# Power.net
KiCad netlist of a schematic drawn in Altium Designer
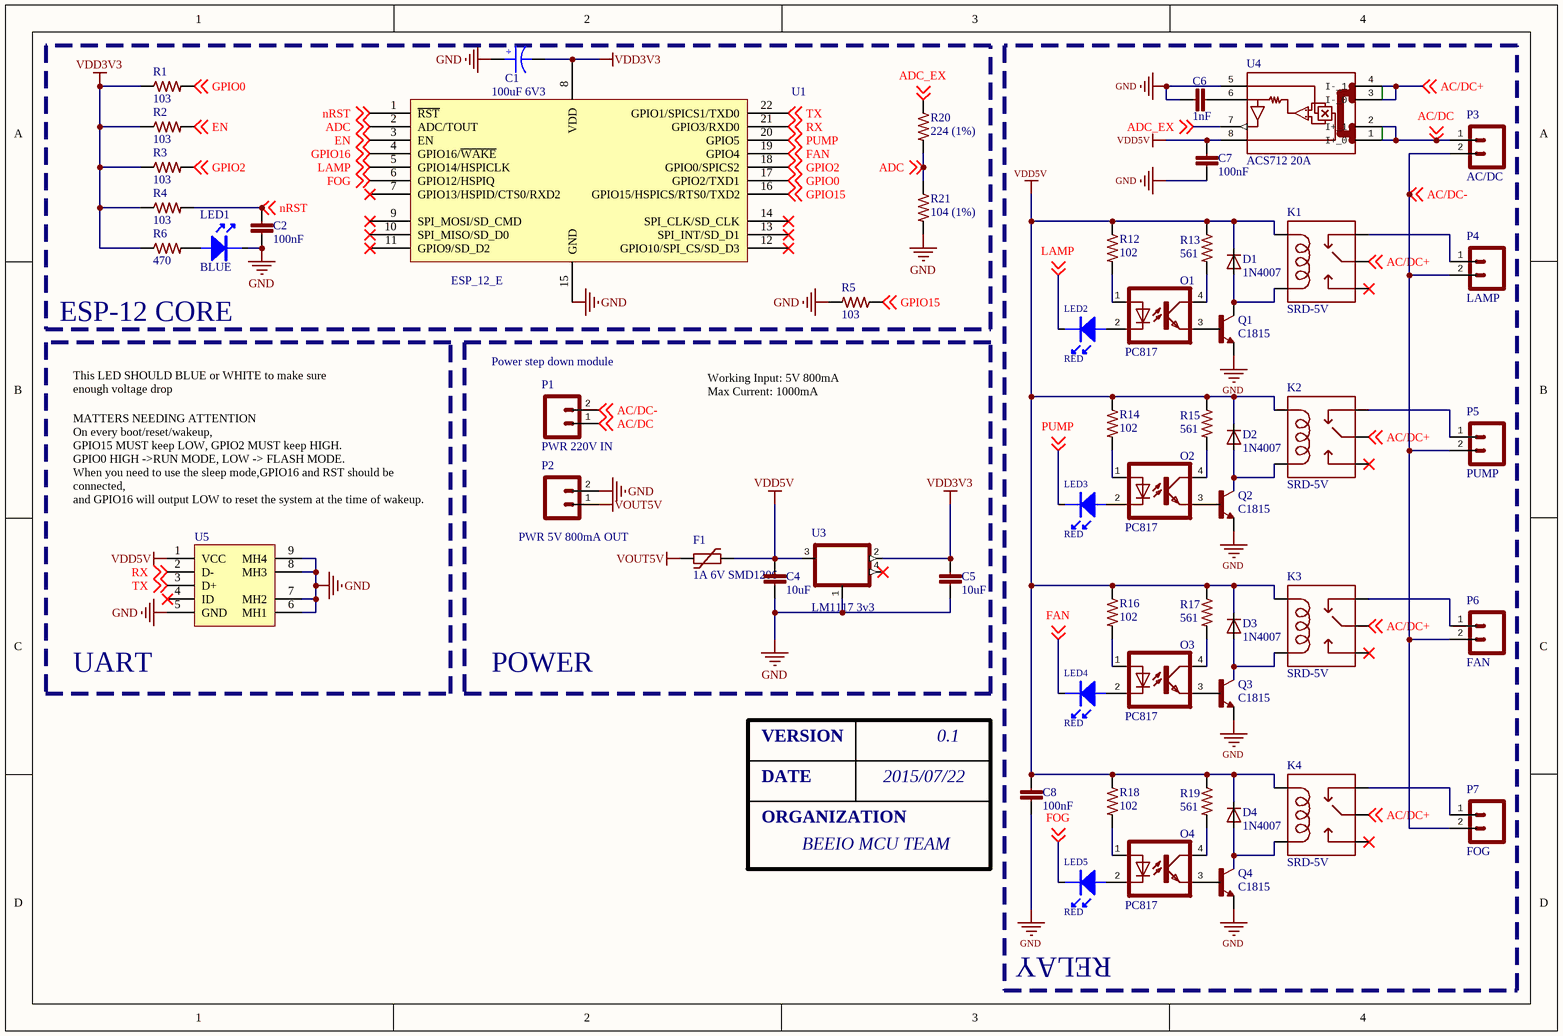
[diagram p0: Power.SchDoc]

(export (version "E")
  (design (tool "Eeschema 10.0.6"))
  (components
    (comp (ref "C1")
      (value "100uF 6V3")
      (footprint "SMT_C_Tantalum_B")
      (description "Capacitor, SM Tantalum; Body 3.5 x 2.8 mm (LxW typ)")
      (libsource (lib "NODEMCU_DEVKIT_V1.0") (part "SMT_C_Tantalum_B"))
    )
    (comp (ref "C2") (value "100nF") (footprint "0603") (libsource (lib "") (part "CAP0603_2")))
    (comp (ref "C4") (value "10uF") (footprint "0603") (libsource (lib "SparkFun") (part "CAP0603")))
    (comp (ref "C5") (value "10uF") (footprint "0603") (libsource (lib "SparkFun") (part "CAP0603")))
    (comp (ref "C6") (value "1nF") (footprint "0603") (libsource (lib "") (part "CAP0603_1")))
    (comp (ref "C7") (value "100nF") (footprint "0603") (libsource (lib "SparkFun") (part "CAP0603")))
    (comp (ref "C8") (value "100nF") (footprint "0603") (libsource (lib "SparkFun") (part "CAP0603")))
    (comp (ref "D1") (value "1N4007") (footprint "SMA-DIODE") (libsource (lib "SparkFun") (part "DIODESMA")))
    (comp (ref "D2") (value "1N4007") (footprint "SMA-DIODE") (libsource (lib "SparkFun") (part "DIODESMA")))
    (comp (ref "D3") (value "1N4007") (footprint "SMA-DIODE") (libsource (lib "SparkFun") (part "DIODESMA")))
    (comp (ref "D4") (value "1N4007") (footprint "SMA-DIODE") (libsource (lib "SparkFun") (part "DIODESMA")))
    (comp (ref "F1")
      (value "1A 6V SMD1206")
      (footprint "1206L")
      (libsource (lib "ptc-littlefuse") (part "1206L"))
    )
    (comp (ref "K1")
      (value "SRD-5V")
      (footprint "SRD-05VDC-SL-C")
      (libsource (lib "SRD-05VDC-SL-C") (part "RELAYPTH"))
    )
    (comp (ref "K2")
      (value "SRD-5V")
      (footprint "SRD-05VDC-SL-C")
      (libsource (lib "SRD-05VDC-SL-C") (part "RELAYPTH"))
    )
    (comp (ref "K3")
      (value "SRD-5V")
      (footprint "SRD-05VDC-SL-C")
      (libsource (lib "SRD-05VDC-SL-C") (part "RELAYPTH"))
    )
    (comp (ref "K4")
      (value "SRD-5V")
      (footprint "SRD-05VDC-SL-C")
      (libsource (lib "SRD-05VDC-SL-C") (part "RELAYPTH"))
    )
    (comp (ref "LED1")
      (value "BLUE")
      (footprint "SMT_LED_0603")
      (description "SMT LED")
      (libsource (lib "NODEMCU_ESP12") (part "SMT_LED_0603"))
    )
    (comp (ref "LED2")
      (value "RED")
      (footprint "SMT_LED_0603")
      (description "SMT LED")
      (libsource (lib "NODEMCU_DEVKIT_V1.0") (part "SMT_LED_0603"))
    )
    (comp (ref "LED3")
      (value "RED")
      (footprint "SMT_LED_0603")
      (description "SMT LED")
      (libsource (lib "NODEMCU_DEVKIT_V1.0") (part "SMT_LED_0603"))
    )
    (comp (ref "LED4")
      (value "RED")
      (footprint "SMT_LED_0603")
      (description "SMT LED")
      (libsource (lib "NODEMCU_DEVKIT_V1.0") (part "SMT_LED_0603"))
    )
    (comp (ref "LED5")
      (value "RED")
      (footprint "SMT_LED_0603")
      (description "SMT LED")
      (libsource (lib "NODEMCU_DEVKIT_V1.0") (part "SMT_LED_0603"))
    )
    (comp (ref "O1")
      (value "PC817")
      (footprint "DIL4-SMD")
      (fields (field (name "MPN") "PC817X4J000F"))
      (libsource (lib "optocoupler") (part "PC817"))
    )
    (comp (ref "O2")
      (value "PC817")
      (footprint "DIL4-SMD")
      (fields (field (name "MPN") "PC817X4J000F"))
      (libsource (lib "optocoupler") (part "PC817"))
    )
    (comp (ref "O3")
      (value "PC817")
      (footprint "DIL4-SMD")
      (fields (field (name "MPN") "PC817X4J000F"))
      (libsource (lib "optocoupler") (part "PC817"))
    )
    (comp (ref "O4")
      (value "PC817")
      (footprint "DIL4-SMD")
      (fields (field (name "MPN") "PC817X4J000F"))
      (libsource (lib "optocoupler") (part "PC817"))
    )
    (comp (ref "P1")
      (value "PWR 220V IN")
      (footprint "SCREWTERMINAL-5MM-2")
      (libsource (lib "SparkFun") (part "M025MM"))
    )
    (comp (ref "P2")
      (value "PWR 5V 800mA OUT")
      (footprint "SCREWTERMINAL-3.5MM-2")
      (libsource (lib "SparkFun") (part "M023.5MM"))
    )
    (comp (ref "P3")
      (value "AC/DC")
      (footprint "SCREWTERMINAL-5MM-2")
      (libsource (lib "SparkFun") (part "M025MM"))
    )
    (comp (ref "P4")
      (value "LAMP")
      (footprint "SCREWTERMINAL-5MM-2")
      (libsource (lib "SparkFun") (part "M025MM"))
    )
    (comp (ref "P5")
      (value "PUMP")
      (footprint "SCREWTERMINAL-5MM-2")
      (libsource (lib "SparkFun") (part "M025MM"))
    )
    (comp (ref "P6")
      (value "FAN")
      (footprint "SCREWTERMINAL-5MM-2")
      (libsource (lib "SparkFun") (part "M025MM"))
    )
    (comp (ref "P7")
      (value "FOG")
      (footprint "SCREWTERMINAL-5MM-2")
      (libsource (lib "SparkFun") (part "M025MM"))
    )
    (comp (ref "Q1")
      (value "C1815")
      (footprint "SOT23")
      (libsource (lib "SparkFun") (part "TRANSISTOR_NPNSOT23"))
    )
    (comp (ref "Q2")
      (value "C1815")
      (footprint "SOT23")
      (libsource (lib "SparkFun") (part "TRANSISTOR_NPNSOT23"))
    )
    (comp (ref "Q3")
      (value "C1815")
      (footprint "SOT23")
      (libsource (lib "SparkFun") (part "TRANSISTOR_NPNSOT23"))
    )
    (comp (ref "Q4")
      (value "C1815")
      (footprint "SOT23")
      (libsource (lib "SparkFun") (part "TRANSISTOR_NPNSOT23"))
    )
    (comp (ref "R1") (value "103") (footprint "0603") (libsource (lib "SparkFun") (part "RESISTOR0603")))
    (comp (ref "R2") (value "103") (footprint "0603") (libsource (lib "SparkFun") (part "RESISTOR0603")))
    (comp (ref "R3") (value "103") (footprint "0603") (libsource (lib "SparkFun") (part "RESISTOR0603")))
    (comp (ref "R4") (value "103") (footprint "0603") (libsource (lib "SparkFun") (part "RESISTOR0603")))
    (comp (ref "R5") (value "103") (footprint "0603") (libsource (lib "SparkFun") (part "RESISTOR0603")))
    (comp (ref "R6") (value "470") (footprint "0603") (libsource (lib "SparkFun") (part "RESISTOR0603")))
    (comp (ref "R12") (value "102") (footprint "0603") (libsource (lib "SparkFun") (part "RESISTOR0603")))
    (comp (ref "R13") (value "561") (footprint "0603") (libsource (lib "SparkFun") (part "RESISTOR0603")))
    (comp (ref "R14") (value "102") (footprint "0603") (libsource (lib "SparkFun") (part "RESISTOR0603")))
    (comp (ref "R15") (value "561") (footprint "0603") (libsource (lib "SparkFun") (part "RESISTOR0603")))
    (comp (ref "R16") (value "102") (footprint "0603") (libsource (lib "SparkFun") (part "RESISTOR0603")))
    (comp (ref "R17") (value "561") (footprint "0603") (libsource (lib "SparkFun") (part "RESISTOR0603")))
    (comp (ref "R18") (value "102") (footprint "0603") (libsource (lib "SparkFun") (part "RESISTOR0603")))
    (comp (ref "R19") (value "561") (footprint "0603") (libsource (lib "SparkFun") (part "RESISTOR0603")))
    (comp (ref "R20")
      (value "224 (1%)")
      (footprint "0603")
      (libsource (lib "SparkFun") (part "RESISTOR0603"))
    )
    (comp (ref "R21")
      (value "104 (1%)")
      (footprint "0603")
      (libsource (lib "SparkFun") (part "RESISTOR0603"))
    )
    (comp (ref "U1")
      (value "ESP_12_E")
      (footprint "ESP_12_E_L")
      (description "ESP-12 Wi-Fi Module by AI-Thinker")
      (libsource (lib "NODEMCU_DEVKIT_V1.0") (part "ESP_12_E"))
    )
    (comp (ref "U3")
      (value "LM1117 3v3")
      (footprint "SOT223")
      (libsource (lib "SparkFun-PowerIC") (part "V_REG_LM1117SOT223"))
    )
    (comp (ref "U4") (value "ACS712 20A") (footprint "SO08") (libsource (lib "ACS712") (part "ACS712")))
    (comp (ref "U5")
      (value "Micro USB B 5S DIP")
      (footprint "USB_MICRO_5S_B")
      (description "USB micro female SMT with 4 fixed foot")
      (libsource (lib "NODEMCU_DEVKIT_V1.0") (part "USB_Micro_5S_B"))
    )
  )
  (nets
    (net (code "1") (name "AC{slash}DC") (class "Default")
      (node (ref "P1") (pin "1") (pinfunction "1_1") (pintype "passive"))
      (node (ref "P3") (pin "1") (pinfunction "1_1") (pintype "passive"))
      (node (ref "U4") (pin "1") (pinfunction "I+_0_1") (pintype "passive"))
      (node (ref "U4") (pin "2") (pinfunction "I+_1_2") (pintype "passive"))
    )
    (net (code "2") (name "AC{slash}DC+") (class "Default")
      (node (ref "K1") (pin "SWCOMMON") (pinfunction "SWCOMMON_SWCOMMON") (pintype "passive"))
      (node (ref "K2") (pin "SWCOMMON") (pinfunction "SWCOMMON_SWCOMMON") (pintype "passive"))
      (node (ref "K3") (pin "SWCOMMON") (pinfunction "SWCOMMON_SWCOMMON") (pintype "passive"))
      (node (ref "K4") (pin "SWCOMMON") (pinfunction "SWCOMMON_SWCOMMON") (pintype "passive"))
      (node (ref "U4") (pin "3") (pinfunction "I-_0_3") (pintype "passive"))
      (node (ref "U4") (pin "4") (pinfunction "I-_1_4") (pintype "passive"))
    )
    (net (code "3") (name "AC{slash}DC-") (class "Default")
      (node (ref "P1") (pin "2") (pinfunction "2_2") (pintype "passive"))
      (node (ref "P3") (pin "2") (pinfunction "2_2") (pintype "passive"))
      (node (ref "P4") (pin "2") (pinfunction "2_2") (pintype "passive"))
      (node (ref "P5") (pin "2") (pinfunction "2_2") (pintype "passive"))
      (node (ref "P6") (pin "2") (pinfunction "2_2") (pintype "passive"))
      (node (ref "P7") (pin "2") (pinfunction "2_2") (pintype "passive"))
    )
    (net (code "4") (name "ADC") (class "Default")
      (node (ref "R20") (pin "2") (pinfunction "2_2") (pintype "passive"))
      (node (ref "R21") (pin "1") (pinfunction "1_1") (pintype "passive"))
      (node (ref "U1") (pin "2") (pinfunction "ADC/TOUT_2") (pintype "passive"))
    )
    (net (code "5") (name "ADC_EX") (class "Default")
      (node (ref "R20") (pin "1") (pinfunction "1_1") (pintype "passive"))
      (node (ref "U4") (pin "7") (pinfunction "VOUT_7") (pintype "output"))
    )
    (net (code "6") (name "EN") (class "Default")
      (node (ref "R2") (pin "2") (pinfunction "2_2") (pintype "passive"))
      (node (ref "U1") (pin "3") (pinfunction "EN_3") (pintype "passive"))
    )
    (net (code "7") (name "FAN") (class "Default")
      (node (ref "LED4") (pin "2") (pinfunction "K_2") (pintype "passive"))
      (node (ref "U1") (pin "19") (pinfunction "GPIO4_19") (pintype "passive"))
    )
    (net (code "8") (name "FOG") (class "Default")
      (node (ref "LED5") (pin "2") (pinfunction "K_2") (pintype "passive"))
      (node (ref "U1") (pin "6") (pinfunction "GPIO12/HSPIQ_6") (pintype "passive"))
    )
    (net (code "9") (name "GND") (class "Default")
      (node (ref "C1") (pin "1") (pinfunction "1_1") (pintype "passive"))
      (node (ref "C2") (pin "2") (pinfunction "2_2") (pintype "passive"))
      (node (ref "C4") (pin "1") (pinfunction "1_1") (pintype "passive"))
      (node (ref "C5") (pin "1") (pinfunction "1_1") (pintype "passive"))
      (node (ref "C6") (pin "1") (pinfunction "1_1") (pintype "passive"))
      (node (ref "C7") (pin "1") (pinfunction "1_1") (pintype "passive"))
      (node (ref "C8") (pin "1") (pinfunction "1_1") (pintype "passive"))
      (node (ref "LED1") (pin "2") (pinfunction "K_2") (pintype "passive"))
      (node (ref "P2") (pin "2") (pinfunction "2_2") (pintype "passive"))
      (node (ref "Q1") (pin "2") (pinfunction "E_2") (pintype "passive"))
      (node (ref "Q2") (pin "2") (pinfunction "E_2") (pintype "passive"))
      (node (ref "Q3") (pin "2") (pinfunction "E_2") (pintype "passive"))
      (node (ref "Q4") (pin "2") (pinfunction "E_2") (pintype "passive"))
      (node (ref "R21") (pin "2") (pinfunction "2_2") (pintype "passive"))
      (node (ref "R5") (pin "2") (pinfunction "2_2") (pintype "passive"))
      (node (ref "U1") (pin "15") (pinfunction "GND_15") (pintype "passive"))
      (node (ref "U3") (pin "1") (pinfunction "ADJ_1") (pintype "passive"))
      (node (ref "U4") (pin "5") (pinfunction "GND_5") (pintype "power_in"))
      (node (ref "U5") (pin "5") (pinfunction "GND_5") (pintype "passive"))
      (node (ref "U5") (pin "6") (pinfunction "MH1_6") (pintype "passive"))
      (node (ref "U5") (pin "7") (pinfunction "MH2_7") (pintype "passive"))
      (node (ref "U5") (pin "8") (pinfunction "MH3_8") (pintype "passive"))
      (node (ref "U5") (pin "9") (pinfunction "MH4_9") (pintype "passive"))
    )
    (net (code "10") (name "GPIO0") (class "Default")
      (node (ref "R1") (pin "2") (pinfunction "2_2") (pintype "passive"))
      (node (ref "U1") (pin "17") (pinfunction "GPIO2/TXD1_17") (pintype "passive"))
    )
    (net (code "11") (name "GPIO2") (class "Default")
      (node (ref "R3") (pin "2") (pinfunction "2_2") (pintype "passive"))
      (node (ref "U1") (pin "18") (pinfunction "GPIO0/SPICS2_18") (pintype "passive"))
    )
    (net (code "12") (name "GPIO15") (class "Default")
      (node (ref "R5") (pin "1") (pinfunction "1_1") (pintype "passive"))
      (node (ref "U1") (pin "16") (pinfunction "GPIO15/HSPICS/RTS0/TXD2_16") (pintype "passive"))
    )
    (net (code "13") (name "GPIO16") (class "Default")
      (node (ref "U1") (pin "4") (pinfunction "GPIO16/~{WAKE}_4") (pintype "passive"))
    )
    (net (code "14") (name "LAMP") (class "Default")
      (node (ref "LED2") (pin "2") (pinfunction "K_2") (pintype "passive"))
      (node (ref "U1") (pin "5") (pinfunction "GPIO14/HSPICLK_5") (pintype "passive"))
    )
    (net (code "15") (name "Net-(K1-SWCLOSE)") (class "Default")
      (node (ref "K1") (pin "SWCLOSED") (pinfunction "SWCLOSE_SWCLOSED") (pintype "passive"))
      (node (ref "P4") (pin "1") (pinfunction "1_1") (pintype "passive"))
    )
    (net (code "16") (name "Net-(K2-SWCLOSE)") (class "Default")
      (node (ref "K2") (pin "SWCLOSED") (pinfunction "SWCLOSE_SWCLOSED") (pintype "passive"))
      (node (ref "P5") (pin "1") (pinfunction "1_1") (pintype "passive"))
    )
    (net (code "17") (name "Net-(K3-SWCLOSE)") (class "Default")
      (node (ref "K3") (pin "SWCLOSED") (pinfunction "SWCLOSE_SWCLOSED") (pintype "passive"))
      (node (ref "P6") (pin "1") (pinfunction "1_1") (pintype "passive"))
    )
    (net (code "18") (name "Net-(K4-SWCLOSE)") (class "Default")
      (node (ref "K4") (pin "SWCLOSED") (pinfunction "SWCLOSE_SWCLOSED") (pintype "passive"))
      (node (ref "P7") (pin "1") (pinfunction "1_1") (pintype "passive"))
    )
    (net (code "19") (name "Net-(LED1-A)") (class "Default")
      (node (ref "LED1") (pin "1") (pinfunction "A_1") (pintype "passive"))
      (node (ref "R6") (pin "2") (pinfunction "2_2") (pintype "passive"))
    )
    (net (code "20") (name "Net-(LED2-A)") (class "Default")
      (node (ref "LED2") (pin "1") (pinfunction "A_1") (pintype "passive"))
      (node (ref "O1") (pin "2") (pinfunction "C_2") (pintype "passive"))
    )
    (net (code "21") (name "Net-(LED3-A)") (class "Default")
      (node (ref "LED3") (pin "1") (pinfunction "A_1") (pintype "passive"))
      (node (ref "O2") (pin "2") (pinfunction "C_2") (pintype "passive"))
    )
    (net (code "22") (name "Net-(LED4-A)") (class "Default")
      (node (ref "LED4") (pin "1") (pinfunction "A_1") (pintype "passive"))
      (node (ref "O3") (pin "2") (pinfunction "C_2") (pintype "passive"))
    )
    (net (code "23") (name "Net-(LED5-A)") (class "Default")
      (node (ref "LED5") (pin "1") (pinfunction "A_1") (pintype "passive"))
      (node (ref "O4") (pin "2") (pinfunction "C_2") (pintype "passive"))
    )
    (net (code "24") (name "Net-(O1-A)") (class "Default")
      (node (ref "O1") (pin "1") (pinfunction "A_1") (pintype "passive"))
      (node (ref "R12") (pin "2") (pinfunction "2_2") (pintype "passive"))
    )
    (net (code "25") (name "Net-(O1-COL)") (class "Default")
      (node (ref "O1") (pin "4") (pinfunction "COL_4") (pintype "passive"))
      (node (ref "R13") (pin "2") (pinfunction "2_2") (pintype "passive"))
    )
    (net (code "26") (name "Net-(O1-EMIT)") (class "Default")
      (node (ref "O1") (pin "3") (pinfunction "EMIT_3") (pintype "passive"))
      (node (ref "Q1") (pin "1") (pinfunction "B_1") (pintype "passive"))
    )
    (net (code "27") (name "Net-(O2-A)") (class "Default")
      (node (ref "O2") (pin "1") (pinfunction "A_1") (pintype "passive"))
      (node (ref "R14") (pin "2") (pinfunction "2_2") (pintype "passive"))
    )
    (net (code "28") (name "Net-(O2-COL)") (class "Default")
      (node (ref "O2") (pin "4") (pinfunction "COL_4") (pintype "passive"))
      (node (ref "R15") (pin "2") (pinfunction "2_2") (pintype "passive"))
    )
    (net (code "29") (name "Net-(O2-EMIT)") (class "Default")
      (node (ref "O2") (pin "3") (pinfunction "EMIT_3") (pintype "passive"))
      (node (ref "Q2") (pin "1") (pinfunction "B_1") (pintype "passive"))
    )
    (net (code "30") (name "Net-(O3-A)") (class "Default")
      (node (ref "O3") (pin "1") (pinfunction "A_1") (pintype "passive"))
      (node (ref "R16") (pin "2") (pinfunction "2_2") (pintype "passive"))
    )
    (net (code "31") (name "Net-(O3-COL)") (class "Default")
      (node (ref "O3") (pin "4") (pinfunction "COL_4") (pintype "passive"))
      (node (ref "R17") (pin "2") (pinfunction "2_2") (pintype "passive"))
    )
    (net (code "32") (name "Net-(O3-EMIT)") (class "Default")
      (node (ref "O3") (pin "3") (pinfunction "EMIT_3") (pintype "passive"))
      (node (ref "Q3") (pin "1") (pinfunction "B_1") (pintype "passive"))
    )
    (net (code "33") (name "Net-(O4-A)") (class "Default")
      (node (ref "O4") (pin "1") (pinfunction "A_1") (pintype "passive"))
      (node (ref "R18") (pin "2") (pinfunction "2_2") (pintype "passive"))
    )
    (net (code "34") (name "Net-(O4-COL)") (class "Default")
      (node (ref "O4") (pin "4") (pinfunction "COL_4") (pintype "passive"))
      (node (ref "R19") (pin "2") (pinfunction "2_2") (pintype "passive"))
    )
    (net (code "35") (name "Net-(O4-EMIT)") (class "Default")
      (node (ref "O4") (pin "3") (pinfunction "EMIT_3") (pintype "passive"))
      (node (ref "Q4") (pin "1") (pinfunction "B_1") (pintype "passive"))
    )
    (net (code "36") (name "Net-(Q1-C)") (class "Default")
      (node (ref "D1") (pin "A") (pinfunction "A_A") (pintype "passive"))
      (node (ref "K1") (pin "COIL0") (pinfunction "COIL0_COIL0") (pintype "passive"))
      (node (ref "Q1") (pin "3") (pinfunction "C_3") (pintype "passive"))
    )
    (net (code "37") (name "Net-(Q2-C)") (class "Default")
      (node (ref "D2") (pin "A") (pinfunction "A_A") (pintype "passive"))
      (node (ref "K2") (pin "COIL0") (pinfunction "COIL0_COIL0") (pintype "passive"))
      (node (ref "Q2") (pin "3") (pinfunction "C_3") (pintype "passive"))
    )
    (net (code "38") (name "Net-(Q3-C)") (class "Default")
      (node (ref "D3") (pin "A") (pinfunction "A_A") (pintype "passive"))
      (node (ref "K3") (pin "COIL0") (pinfunction "COIL0_COIL0") (pintype "passive"))
      (node (ref "Q3") (pin "3") (pinfunction "C_3") (pintype "passive"))
    )
    (net (code "39") (name "Net-(Q4-C)") (class "Default")
      (node (ref "D4") (pin "A") (pinfunction "A_A") (pintype "passive"))
      (node (ref "K4") (pin "COIL0") (pinfunction "COIL0_COIL0") (pintype "passive"))
      (node (ref "Q4") (pin "3") (pinfunction "C_3") (pintype "passive"))
    )
    (net (code "40") (name "Net-(U4-FILTER)") (class "Default")
      (node (ref "C6") (pin "2") (pinfunction "2_2") (pintype "passive"))
      (node (ref "U4") (pin "6") (pinfunction "FILTER_6") (pintype "passive"))
    )
    (net (code "41") (name "PUMP") (class "Default")
      (node (ref "LED3") (pin "2") (pinfunction "K_2") (pintype "passive"))
      (node (ref "U1") (pin "20") (pinfunction "GPIO5_20") (pintype "passive"))
    )
    (net (code "42") (name "RX") (class "Default")
      (node (ref "U1") (pin "21") (pinfunction "GPIO3/RXD0_21") (pintype "passive"))
      (node (ref "U5") (pin "2") (pinfunction "D-_2") (pintype "passive"))
    )
    (net (code "43") (name "TX") (class "Default")
      (node (ref "U1") (pin "22") (pinfunction "GPIO1/SPICS1/TXD0_22") (pintype "passive"))
      (node (ref "U5") (pin "3") (pinfunction "D+_3") (pintype "passive"))
    )
    (net (code "44") (name "VDD3V3") (class "Default")
      (node (ref "C1") (pin "2") (pinfunction "2_2") (pintype "passive"))
      (node (ref "C5") (pin "2") (pinfunction "2_2") (pintype "passive"))
      (node (ref "R1") (pin "1") (pinfunction "1_1") (pintype "passive"))
      (node (ref "R2") (pin "1") (pinfunction "1_1") (pintype "passive"))
      (node (ref "R3") (pin "1") (pinfunction "1_1") (pintype "passive"))
      (node (ref "R4") (pin "1") (pinfunction "1_1") (pintype "passive"))
      (node (ref "R6") (pin "1") (pinfunction "1_1") (pintype "passive"))
      (node (ref "U1") (pin "8") (pinfunction "VDD_8") (pintype "passive"))
      (node (ref "U3") (pin "2") (pinfunction "OUT_2") (pintype "output"))
    )
    (net (code "45") (name "VDD5V") (class "Default")
      (node (ref "C4") (pin "2") (pinfunction "2_2") (pintype "passive"))
      (node (ref "C7") (pin "2") (pinfunction "2_2") (pintype "passive"))
      (node (ref "C8") (pin "2") (pinfunction "2_2") (pintype "passive"))
      (node (ref "D1") (pin "C") (pinfunction "C_C") (pintype "passive"))
      (node (ref "D2") (pin "C") (pinfunction "C_C") (pintype "passive"))
      (node (ref "D3") (pin "C") (pinfunction "C_C") (pintype "passive"))
      (node (ref "D4") (pin "C") (pinfunction "C_C") (pintype "passive"))
      (node (ref "F1") (pin "P$2") (pinfunction "2_P$2") (pintype "passive"))
      (node (ref "K1") (pin "COIL1") (pinfunction "COIL1_COIL1") (pintype "passive"))
      (node (ref "K2") (pin "COIL1") (pinfunction "COIL1_COIL1") (pintype "passive"))
      (node (ref "K3") (pin "COIL1") (pinfunction "COIL1_COIL1") (pintype "passive"))
      (node (ref "K4") (pin "COIL1") (pinfunction "COIL1_COIL1") (pintype "passive"))
      (node (ref "R12") (pin "1") (pinfunction "1_1") (pintype "passive"))
      (node (ref "R13") (pin "1") (pinfunction "1_1") (pintype "passive"))
      (node (ref "R14") (pin "1") (pinfunction "1_1") (pintype "passive"))
      (node (ref "R15") (pin "1") (pinfunction "1_1") (pintype "passive"))
      (node (ref "R16") (pin "1") (pinfunction "1_1") (pintype "passive"))
      (node (ref "R17") (pin "1") (pinfunction "1_1") (pintype "passive"))
      (node (ref "R18") (pin "1") (pinfunction "1_1") (pintype "passive"))
      (node (ref "R19") (pin "1") (pinfunction "1_1") (pintype "passive"))
      (node (ref "U3") (pin "3") (pinfunction "IN_3") (pintype "passive"))
      (node (ref "U4") (pin "8") (pinfunction "VCC_8") (pintype "power_in"))
      (node (ref "U5") (pin "1") (pinfunction "VCC_1") (pintype "passive"))
    )
    (net (code "46") (name "VOUT5V") (class "Default")
      (node (ref "F1") (pin "P$1") (pinfunction "1_P$1") (pintype "passive"))
      (node (ref "P2") (pin "1") (pinfunction "1_1") (pintype "passive"))
    )
    (net (code "47") (name "nRST") (class "Default")
      (node (ref "C2") (pin "1") (pinfunction "1_1") (pintype "passive"))
      (node (ref "R4") (pin "2") (pinfunction "2_2") (pintype "passive"))
      (node (ref "U1") (pin "1") (pinfunction "~{RST}_1") (pintype "passive"))
    )
    (net (code "48") (name "unconnected-(K1-PadSWOPEN)") (class "Default")
      (node (ref "K1") (pin "SWOPEN") (pinfunction "SWOPEN_SWOPEN") (pintype "passive+no_connect"))
    )
    (net (code "49") (name "unconnected-(K2-PadSWOPEN)") (class "Default")
      (node (ref "K2") (pin "SWOPEN") (pinfunction "SWOPEN_SWOPEN") (pintype "passive+no_connect"))
    )
    (net (code "50") (name "unconnected-(K3-PadSWOPEN)") (class "Default")
      (node (ref "K3") (pin "SWOPEN") (pinfunction "SWOPEN_SWOPEN") (pintype "passive+no_connect"))
    )
    (net (code "51") (name "unconnected-(K4-PadSWOPEN)") (class "Default")
      (node (ref "K4") (pin "SWOPEN") (pinfunction "SWOPEN_SWOPEN") (pintype "passive+no_connect"))
    )
    (net (code "52") (name "unconnected-(U1-GPIO9{slash}SD_D2-Pad11)") (class "Default")
      (node (ref "U1") (pin "11") (pinfunction "GPIO9/SD_D2_11") (pintype "passive+no_connect"))
    )
    (net (code "53") (name "unconnected-(U1-GPIO10{slash}SPI_CS{slash}SD_D3-Pad12)") (class "Default")
      (node (ref "U1") (pin "12") (pinfunction "GPIO10/SPI_CS/SD_D3_12") (pintype "passive+no_connect"))
    )
    (net (code "54") (name "unconnected-(U1-GPIO13{slash}HSPID{slash}CTS0{slash}RXD2-Pad7)") (class "Default")
      (node (ref "U1") (pin "7") (pinfunction "GPIO13/HSPID/CTS0/RXD2_7") (pintype "passive+no_connect"))
    )
    (net (code "55") (name "unconnected-(U1-SPI_CLK{slash}SD_CLK-Pad14)") (class "Default")
      (node (ref "U1") (pin "14") (pinfunction "SPI_CLK/SD_CLK_14") (pintype "passive+no_connect"))
    )
    (net (code "56") (name "unconnected-(U1-SPI_INT{slash}SD_D1-Pad13)") (class "Default")
      (node (ref "U1") (pin "13") (pinfunction "SPI_INT/SD_D1_13") (pintype "passive+no_connect"))
    )
    (net (code "57") (name "unconnected-(U1-SPI_MISO{slash}SD_D0-Pad10)") (class "Default")
      (node (ref "U1") (pin "10") (pinfunction "SPI_MISO/SD_D0_10") (pintype "passive+no_connect"))
    )
    (net (code "58") (name "unconnected-(U1-SPI_MOSI{slash}SD_CMD-Pad9)") (class "Default")
      (node (ref "U1") (pin "9") (pinfunction "SPI_MOSI/SD_CMD_9") (pintype "passive+no_connect"))
    )
    (net (code "59") (name "unconnected-(U3-OUT-Pad4)") (class "Default")
      (node (ref "U3") (pin "4") (pinfunction "OUT_4") (pintype "output+no_connect"))
    )
    (net (code "60") (name "unconnected-(U5-ID-Pad4)") (class "Default")
      (node (ref "U5") (pin "4") (pinfunction "ID_4") (pintype "passive+no_connect"))
    )
  )
)
